# Brakeout_board_-_wire_connection.net
KiCad netlist of a schematic drawn in EAGLE
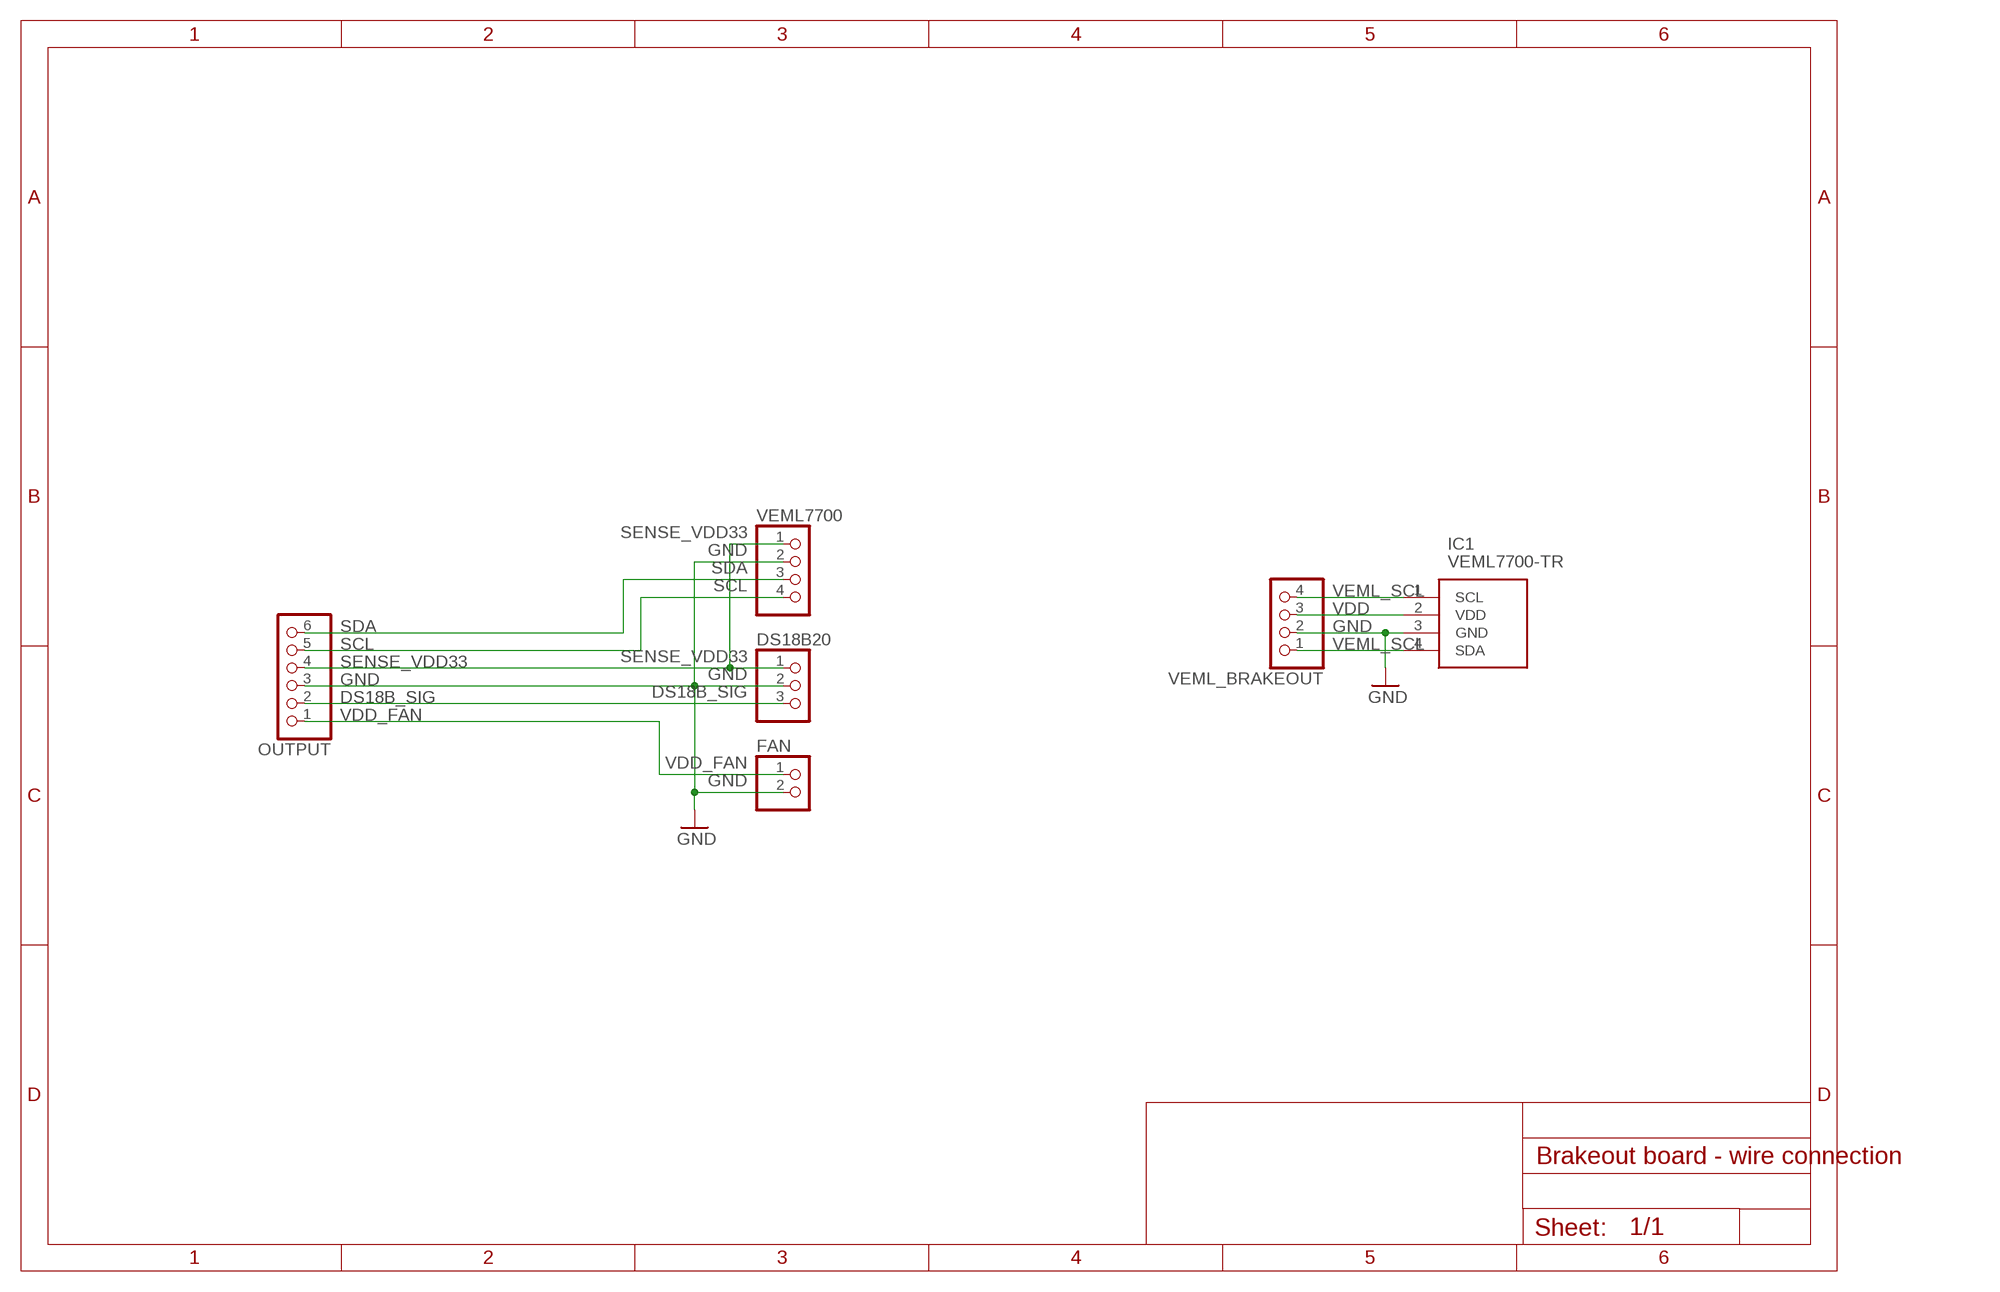
[diagram p0: schematic, sheet 1]

(export (version "E")
  (design (tool "Eeschema 10.0.6"))
  (components
    (comp (ref "DS18B20")
      (value "PINHD-1X3")
      (footprint "eagle-import:1X03")
      (libsource (lib "eagle-import") (part "PINHD-1X3"))
    )
    (comp (ref "FAN")
      (value "PINHD-1X2")
      (footprint "eagle-import:1X02")
      (libsource (lib "eagle-import") (part "PINHD-1X2"))
    )
    (comp (ref "IC1")
      (value "VEML7700-TR")
      (footprint "eagle-import:VEML7700")
      (fields (field (name "MOUSER_PART_NUMBER") "78-VEML7700-TR"))
      (libsource (lib "eagle-import") (part "VEML7700-TR"))
    )
    (comp (ref "OUTPUT")
      (value "PINHD-1X6")
      (footprint "eagle-import:1X06")
      (libsource (lib "eagle-import") (part "PINHD-1X6"))
    )
    (comp (ref "VEML7700")
      (value "PINHD-1X4")
      (footprint "eagle-import:1X04")
      (libsource (lib "eagle-import") (part "PINHD-1X4"))
    )
    (comp (ref "VEML_BRAKEOUT")
      (value "PINHD-1X4")
      (footprint "eagle-import:1X04")
      (libsource (lib "eagle-import") (part "PINHD-1X4"))
    )
  )
  (nets
    (net (code "1") (name "/DS18B_SIG") (class "Default")
      (node (ref "DS18B20") (pin "3") (pinfunction "3_3") (pintype "passive"))
      (node (ref "OUTPUT") (pin "2") (pinfunction "2_2") (pintype "passive"))
    )
    (net (code "2") (name "/SCL") (class "Default")
      (node (ref "OUTPUT") (pin "5") (pinfunction "5_5") (pintype "passive"))
      (node (ref "VEML7700") (pin "4") (pinfunction "4_4") (pintype "passive"))
    )
    (net (code "3") (name "/SDA") (class "Default")
      (node (ref "OUTPUT") (pin "6") (pinfunction "6_6") (pintype "passive"))
      (node (ref "VEML7700") (pin "3") (pinfunction "3_3") (pintype "passive"))
    )
    (net (code "4") (name "/SENSE_VDD33") (class "Default")
      (node (ref "DS18B20") (pin "1") (pinfunction "1_1") (pintype "passive"))
      (node (ref "OUTPUT") (pin "4") (pinfunction "4_4") (pintype "passive"))
      (node (ref "VEML7700") (pin "1") (pinfunction "1_1") (pintype "passive"))
    )
    (net (code "5") (name "/VDD") (class "Default")
      (node (ref "IC1") (pin "2") (pinfunction "VDD_2") (pintype "power_in"))
      (node (ref "VEML_BRAKEOUT") (pin "3") (pinfunction "3_3") (pintype "passive"))
    )
    (net (code "6") (name "/VDD_FAN") (class "Default")
      (node (ref "FAN") (pin "1") (pinfunction "1_1") (pintype "passive"))
      (node (ref "OUTPUT") (pin "1") (pinfunction "1_1") (pintype "passive"))
    )
    (net (code "7") (name "/VEML_SCL") (class "Default")
      (node (ref "IC1") (pin "1") (pinfunction "SCL_1") (pintype "bidirectional"))
      (node (ref "IC1") (pin "4") (pinfunction "SDA_4") (pintype "bidirectional"))
      (node (ref "VEML_BRAKEOUT") (pin "1") (pinfunction "1_1") (pintype "passive"))
      (node (ref "VEML_BRAKEOUT") (pin "4") (pinfunction "4_4") (pintype "passive"))
    )
    (net (code "8") (name "GND") (class "Default")
      (node (ref "DS18B20") (pin "2") (pinfunction "2_2") (pintype "passive"))
      (node (ref "FAN") (pin "2") (pinfunction "2_2") (pintype "passive"))
      (node (ref "IC1") (pin "3") (pinfunction "GND_3") (pintype "power_in"))
      (node (ref "OUTPUT") (pin "3") (pinfunction "3_3") (pintype "passive"))
      (node (ref "VEML7700") (pin "2") (pinfunction "2_2") (pintype "passive"))
      (node (ref "VEML_BRAKEOUT") (pin "2") (pinfunction "2_2") (pintype "passive"))
    )
  )
)
